# 13_Raspberry_Misc.net
KiCad netlist of a schematic drawn in Altium Designer
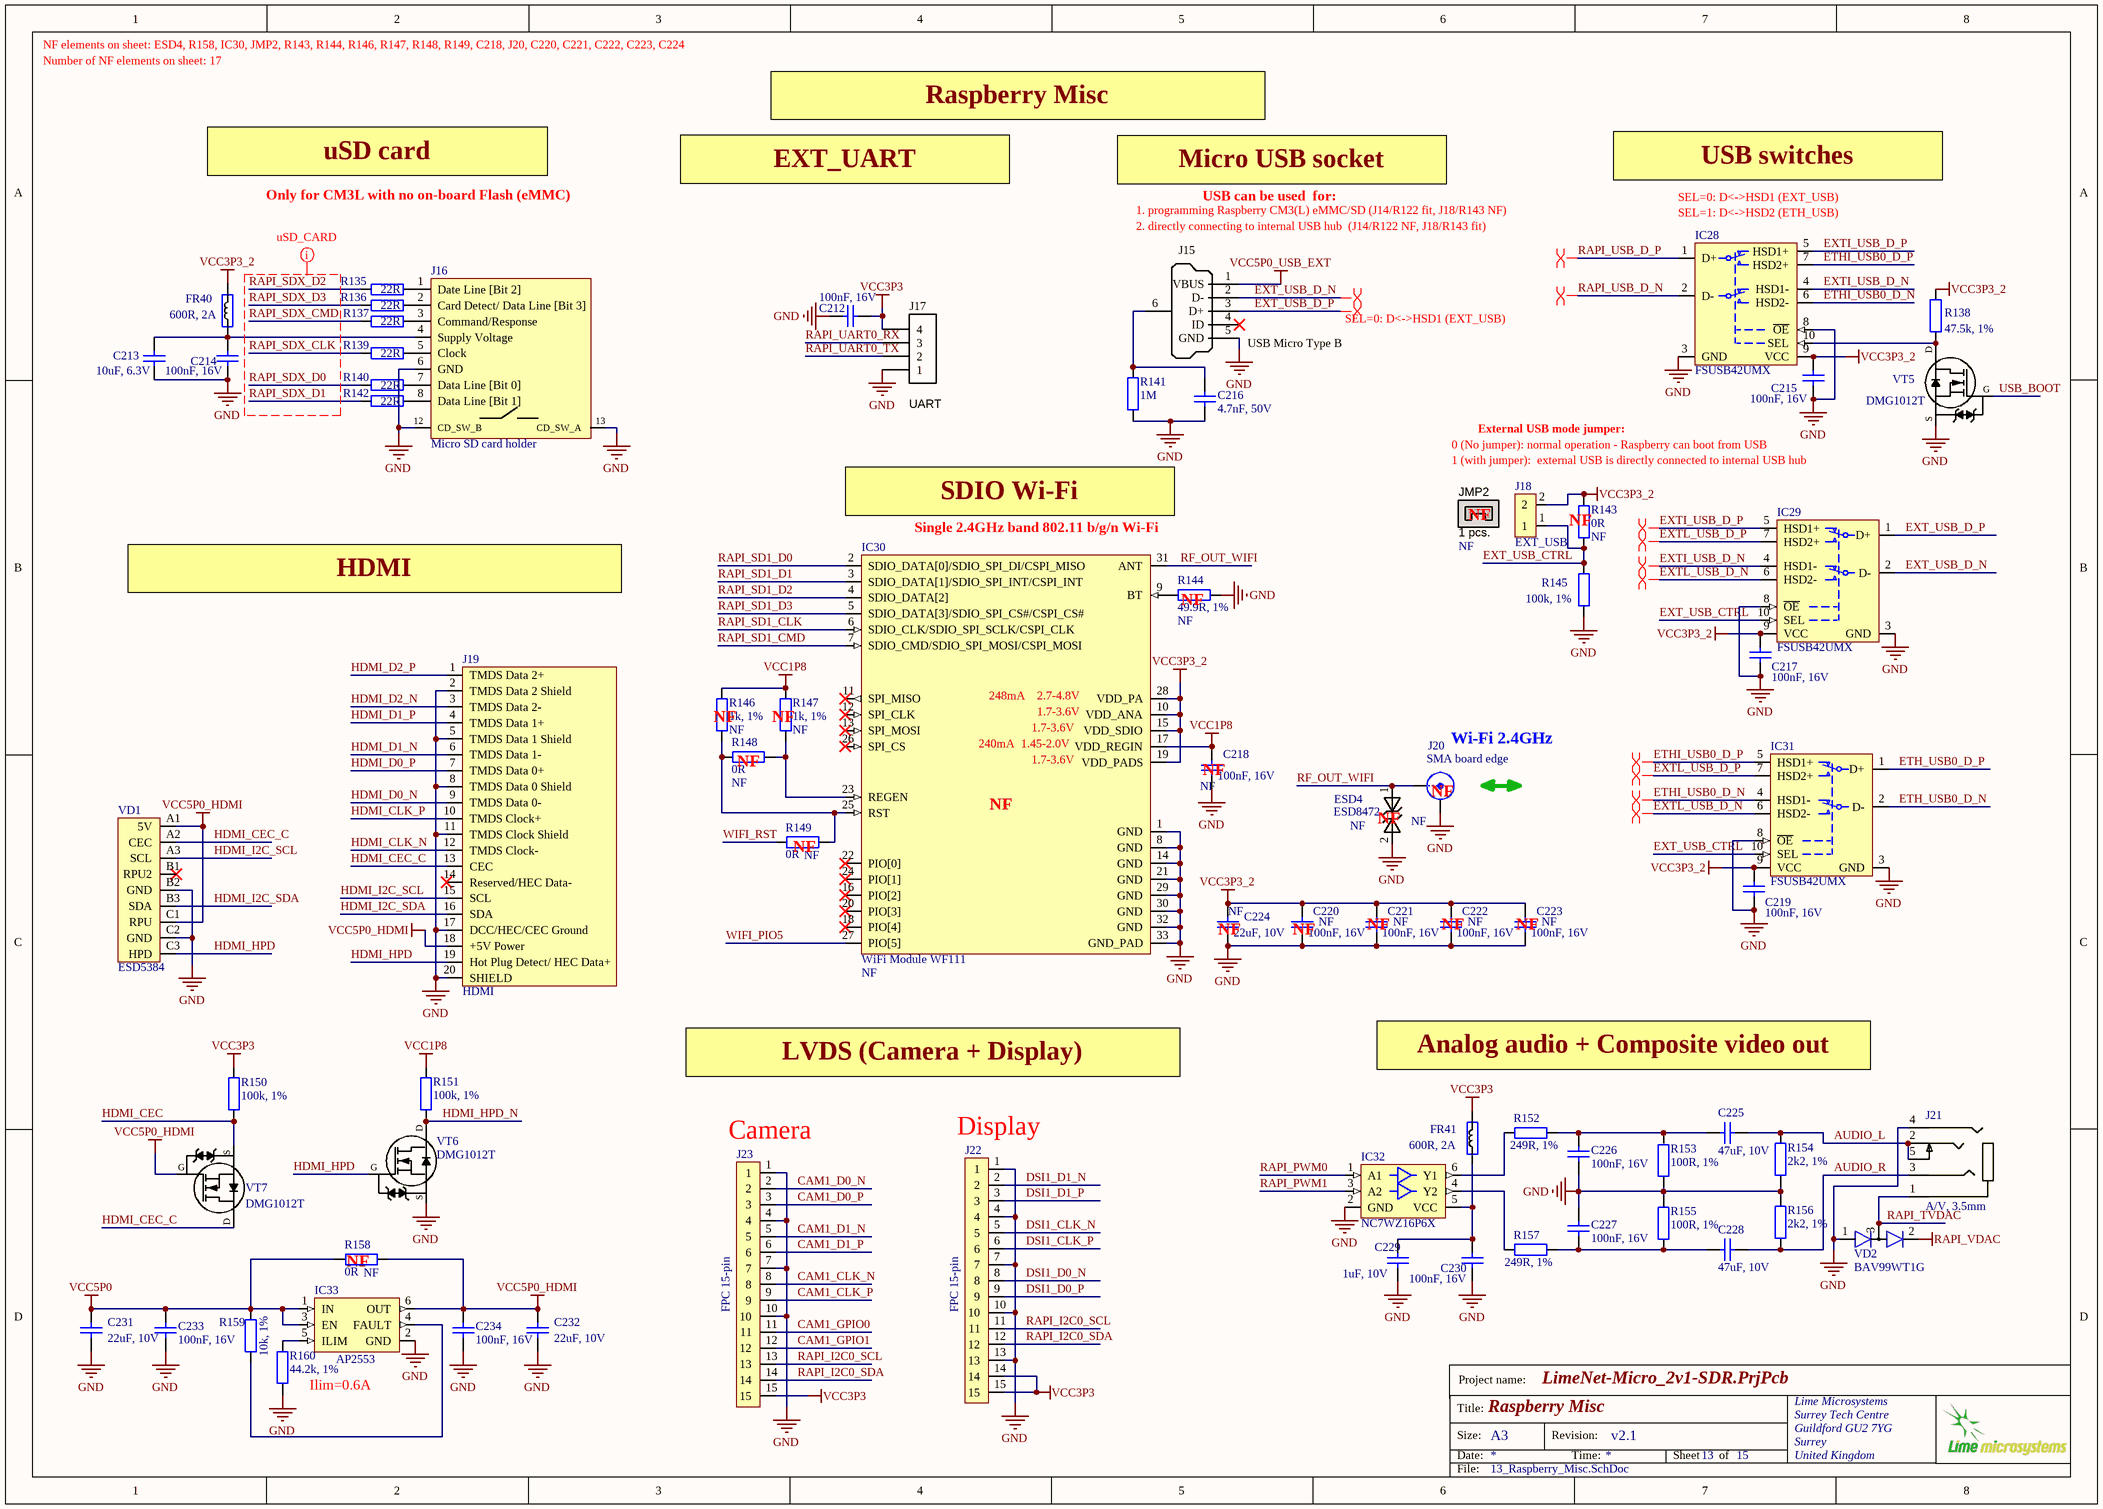
[diagram p0: 13_Raspberry_Misc.SchDoc]

(export (version "E")
  (design (tool "Eeschema 10.0.6"))
  (components
    (comp (ref "C212")
      (value "100nF, 16V")
      (footprint "CAP0402")
      (fields (field (name "TOLERANCE") "10 %") (field (name "MANUFACTURER") "Murata Electronics"))
      (libsource (lib "LimeFPGAboard_schLib") (part "Cap_0603"))
    )
    (comp (ref "C213")
      (value "10uF, 6.3V")
      (footprint "CAP0603")
      (fields (field (name "TOLERANCE") "±20%") (field (name "MANUFACTURER") "Yageo"))
      (libsource (lib "LimeFPGAboard_schLib") (part "Cap_0603"))
    )
    (comp (ref "C214")
      (value "100nF, 16V")
      (footprint "CAP0402")
      (fields (field (name "TOLERANCE") "10 %") (field (name "MANUFACTURER") "Murata Electronics"))
      (libsource (lib "LimeFPGAboard_schLib") (part "Cap_0603"))
    )
    (comp (ref "C215")
      (value "100nF, 16V")
      (footprint "CAP0402")
      (fields
        (field (name "MANUFACTURER") "Murata Electronics")
        (field (name "TOLERANCE") "10 %")
        (field (name "MANUFACTURER PART NUMBER") "GRM155R71C104KA88D")
      )
      (libsource (lib "LimeMicroAltiumLib_schLib") (part "Cap_0402"))
    )
    (comp (ref "C216")
      (value "4.7nF, 50V")
      (footprint "CAP0402")
      (fields
        (field (name "TOLERANCE") "±10%")
        (field (name "MANUFACTURER") "Murata Electronics North America")
      )
      (libsource (lib "LimeMicroAltiumLib_schLib") (part "Cap_0402"))
    )
    (comp (ref "C217")
      (value "100nF, 16V")
      (footprint "CAP0402")
      (fields
        (field (name "MANUFACTURER") "Murata Electronics")
        (field (name "TOLERANCE") "10 %")
        (field (name "MANUFACTURER PART NUMBER") "GRM155R71C104KA88D")
      )
      (libsource (lib "LimeMicroAltiumLib_schLib") (part "Cap_0402"))
    )
    (comp (ref "C218")
      (value "100nF, 16V")
      (footprint "CAP0402")
      (fields
        (field (name "ASSEMBLY INFO") "NF")
        (field (name "MANUFACTURER") "Murata Electronics")
        (field (name "TOLERANCE") "10 %")
        (field (name "MANUFACTURER PART NUMBER") "GRM155R71C104KA88D")
      )
      (libsource (lib "LimeMicroAltiumLib_schLib") (part "Cap_0402"))
    )
    (comp (ref "C219")
      (value "100nF, 16V")
      (footprint "CAP0402")
      (fields
        (field (name "MANUFACTURER") "Murata Electronics")
        (field (name "TOLERANCE") "10 %")
        (field (name "MANUFACTURER PART NUMBER") "GRM155R71C104KA88D")
      )
      (libsource (lib "LimeMicroAltiumLib_schLib") (part "Cap_0402"))
    )
    (comp (ref "C220")
      (value "100nF, 16V")
      (footprint "CAP0402")
      (fields
        (field (name "ASSEMBLY INFO") "NF")
        (field (name "MANUFACTURER") "Murata Electronics")
        (field (name "TOLERANCE") "10 %")
        (field (name "MANUFACTURER PART NUMBER") "GRM155R71C104KA88D")
      )
      (libsource (lib "LimeMicroAltiumLib_schLib") (part "Cap_0402"))
    )
    (comp (ref "C221")
      (value "100nF, 16V")
      (footprint "CAP0402")
      (fields
        (field (name "ASSEMBLY INFO") "NF")
        (field (name "MANUFACTURER") "Murata Electronics")
        (field (name "TOLERANCE") "10 %")
        (field (name "MANUFACTURER PART NUMBER") "GRM155R71C104KA88D")
      )
      (libsource (lib "LimeMicroAltiumLib_schLib") (part "Cap_0402"))
    )
    (comp (ref "C222")
      (value "100nF, 16V")
      (footprint "CAP0402")
      (fields
        (field (name "ASSEMBLY INFO") "NF")
        (field (name "MANUFACTURER") "Murata Electronics")
        (field (name "TOLERANCE") "10 %")
        (field (name "MANUFACTURER PART NUMBER") "GRM155R71C104KA88D")
      )
      (libsource (lib "LimeMicroAltiumLib_schLib") (part "Cap_0402"))
    )
    (comp (ref "C223")
      (value "100nF, 16V")
      (footprint "CAP0402")
      (fields
        (field (name "ASSEMBLY INFO") "NF")
        (field (name "MANUFACTURER") "Murata Electronics")
        (field (name "TOLERANCE") "10 %")
        (field (name "MANUFACTURER PART NUMBER") "GRM155R71C104KA88D")
      )
      (libsource (lib "LimeMicroAltiumLib_schLib") (part "Cap_0402"))
    )
    (comp (ref "C224")
      (value "22uF, 10V")
      (footprint "CAP0603")
      (fields
        (field (name "TOLERANCE") "20 %")
        (field (name "MANUFACTURER") "TDK Corporation")
        (field (name "ASSEMBLY INFO") "NF")
      )
      (libsource (lib "LimeFPGAboard_schLib") (part "Cap_0603"))
    )
    (comp (ref "C225")
      (value "47uF, 10V")
      (footprint "CAP1206")
      (fields (field (name "TOLERANCE") "±20%") (field (name "MANUFACTURER") "TDK Corporation"))
      (libsource (lib "LimeFPGAboard_schLib") (part "Cap_1206"))
    )
    (comp (ref "C226")
      (value "100nF, 16V")
      (footprint "CAP0402")
      (fields
        (field (name "MANUFACTURER") "Murata Electronics")
        (field (name "TOLERANCE") "10 %")
        (field (name "MANUFACTURER PART NUMBER") "GRM155R71C104KA88D")
      )
      (libsource (lib "LimeMicroAltiumLib_schLib") (part "Cap_0402"))
    )
    (comp (ref "C227")
      (value "100nF, 16V")
      (footprint "CAP0402")
      (fields
        (field (name "MANUFACTURER") "Murata Electronics")
        (field (name "TOLERANCE") "10 %")
        (field (name "MANUFACTURER PART NUMBER") "GRM155R71C104KA88D")
      )
      (libsource (lib "LimeMicroAltiumLib_schLib") (part "Cap_0402"))
    )
    (comp (ref "C228")
      (value "47uF, 10V")
      (footprint "CAP1206")
      (fields (field (name "TOLERANCE") "±20%") (field (name "MANUFACTURER") "TDK Corporation"))
      (libsource (lib "LimeFPGAboard_schLib") (part "Cap_1206"))
    )
    (comp (ref "C229")
      (value "1uF, 10V")
      (footprint "CAP0402")
      (description "CAP CER 1UF 10V X5R 0402")
      (fields (field (name "MANUFACTURER") "Yageo") (field (name "TOLERANCE") "±20%"))
      (libsource (lib "LimeMicroAltiumLib_schLib") (part "Cap_0402"))
    )
    (comp (ref "C230")
      (value "100nF, 16V")
      (footprint "CAP0402")
      (fields
        (field (name "MANUFACTURER") "Murata Electronics")
        (field (name "TOLERANCE") "10 %")
        (field (name "MANUFACTURER PART NUMBER") "GRM155R71C104KA88D")
      )
      (libsource (lib "LimeMicroAltiumLib_schLib") (part "Cap_0402"))
    )
    (comp (ref "C231")
      (value "22uF, 10V")
      (footprint "CAP0603")
      (fields (field (name "TOLERANCE") "20 %") (field (name "MANUFACTURER") "TDK Corporation"))
      (libsource (lib "LimeFPGAboard_schLib") (part "Cap_0603"))
    )
    (comp (ref "C232")
      (value "22uF, 10V")
      (footprint "CAP0603")
      (fields (field (name "TOLERANCE") "20 %") (field (name "MANUFACTURER") "TDK Corporation"))
      (libsource (lib "LimeFPGAboard_schLib") (part "Cap_0603"))
    )
    (comp (ref "C233")
      (value "100nF, 16V")
      (footprint "CAP0402")
      (fields
        (field (name "MANUFACTURER") "Murata Electronics")
        (field (name "TOLERANCE") "10 %")
        (field (name "MANUFACTURER PART NUMBER") "GRM155R71C104KA88D")
      )
      (libsource (lib "LimeMicroAltiumLib_schLib") (part "Cap_0402"))
    )
    (comp (ref "C234")
      (value "100nF, 16V")
      (footprint "CAP0402")
      (fields
        (field (name "MANUFACTURER") "Murata Electronics")
        (field (name "TOLERANCE") "10 %")
        (field (name "MANUFACTURER PART NUMBER") "GRM155R71C104KA88D")
      )
      (libsource (lib "LimeMicroAltiumLib_schLib") (part "Cap_0402"))
    )
    (comp (ref "ESD4")
      (value "ESD8472")
      (footprint "ESD8472_X3DFN2")
      (fields (field (name "MANUFACTURER") "ON Semiconductor") (field (name "ASSEMBLY INFO") "NF"))
      (libsource (lib "LimeMicroAltiumLib_schLib") (part "ESD8472"))
    )
    (comp (ref "FR40")
      (value "600R, 2A")
      (footprint "RES0805")
      (fields (field (name "MANUFACTURER") "TDK Corporation"))
      (libsource (lib "LimeMicroAltiumLib_schLib") (part "Ferrite"))
    )
    (comp (ref "FR41")
      (value "600R, 2A")
      (footprint "RES0805")
      (fields (field (name "MANUFACTURER") "TDK Corporation"))
      (libsource (lib "LimeMicroAltiumLib_schLib") (part "Ferrite"))
    )
    (comp (ref "IC28")
      (value "FSUSB42UMX")
      (footprint "FSUSB42UMX")
      (fields (field (name "MANUFACTURER") "ON Semiconductor") (field (name "BASE PART NUMBER") "FSUSB42"))
      (libsource (lib "") (part "FSUSB42UMX_1"))
    )
    (comp (ref "IC29")
      (value "FSUSB42UMX")
      (footprint "FSUSB42UMX")
      (fields (field (name "MANUFACTURER") "ON Semiconductor") (field (name "BASE PART NUMBER") "FSUSB42"))
      (libsource (lib "LimeMicroAltiumLib_schLib_r01") (part "FSUSB42UMX"))
    )
    (comp (ref "IC30")
      (value "WiFi Module WF111")
      (footprint "WF111-A-V1_WIFI")
      (fields (field (name "MANUFACTURER") "Bluegiga Technologies") (field (name "ASSEMBLY INFO") "NF"))
      (libsource (lib "LimeMicroAltiumLib_schLib_r01") (part "WF111-A-V1_WIFI"))
    )
    (comp (ref "IC31")
      (value "FSUSB42UMX")
      (footprint "FSUSB42UMX")
      (fields (field (name "MANUFACTURER") "ON Semiconductor") (field (name "BASE PART NUMBER") "FSUSB42"))
      (libsource (lib "LimeMicroAltiumLib_schLib_r01") (part "FSUSB42UMX"))
    )
    (comp (ref "IC32")
      (value "NC7WZ16P6X")
      (footprint "SC-70_NC7WZ16P6X")
      (fields (field (name "MANUFACTURER") "ON Semiconductor / Fairchild"))
      (libsource (lib "LimeMicroAltiumLib_schLib_r01") (part "NC7WZ16P6X_DUAL_BUFFER"))
    )
    (comp (ref "IC33")
      (value "AP2553")
      (footprint "SOT23-6")
      (fields (field (name "MANUFACTURER") "Diodes") (field (name "VOLTAGE") "5.5V"))
      (libsource (lib "LimeMicroAltiumLib_schLib_r01") (part "AP2553W6-7"))
    )
    (comp (ref "J15")
      (value "USB Micro Type B")
      (footprint "microUSB_v2")
      (description "Connector SMD USB Micro Type B")
      (fields (field (name "MANUFACTURER") "Amphenol FCI"))
      (libsource (lib "LimeMicroAltiumLib_schLib") (part "USB_Micro_TypeB"))
    )
    (comp (ref "J16")
      (value "Micro SD card holder")
      (footprint "MICRO_SD_CARD_114-00841-68_v2")
      (fields (field (name "MANUFACTURER") "Amphenol Commercial Products"))
      (libsource (lib "LimeMicroAltiumLib_schLib_r01") (part "MICRO_SD_114-00841-68"))
    )
    (comp (ref "J17")
      (value "UART")
      (footprint "HEADER4X1_TH")
      (description "Header, 4-pin")
      (fields (field (name "MANUFACTURER") "Wurth Electronics Inc."))
      (libsource (lib "LimeMicroAltiumLib_schLib") (part "Header4P"))
    )
    (comp (ref "J18")
      (value "EXT_USB")
      (footprint "HDR_1x2")
      (fields (field (name "MANUFACTURER") "3M"))
      (libsource (lib "LimeFPGAboard_schLib") (part "Jumper"))
    )
    (comp (ref "J19")
      (value "HDMI")
      (footprint "HDMI_AMPHENOL_10029449-111RLF")
      (fields (field (name "MANUFACTURER") "Amphenol FCI"))
      (libsource (lib "LimeMicroAltiumLib_schLib_r01") (part "HDMI_AMPHENOL_10029449-111RLF"))
    )
    (comp (ref "J20")
      (value "SMA board edge")
      (footprint "SMA_connector_board_edge_SM")
      (description "CONN SMA JACK STR 50OHM EDGE MNT")
      (fields (field (name "ASSEMBLY INFO") "NF") (field (name "MANUFACTURER") "RF Solutions"))
      (libsource (lib "LimeMicroAltiumLib_schLib") (part "RF_IF_connector"))
    )
    (comp (ref "J21")
      (value "A/V, 3.5mm")
      (footprint "Audio_jack_3.5mm")
      (fields (field (name "MANUFACTURER") "CUI Inc."))
      (libsource (lib "LimeMicroAltiumLib_schLib_r01") (part "AUDIO_JACK_3mm5_SJ-4351X"))
    )
    (comp (ref "J22")
      (value "FPC 15-pin")
      (footprint "FPC_CONNECTOR_15pin_1-1734248-5")
      (fields (field (name "MANUFACTURER") "TE Connectivity"))
      (libsource (lib "LimeMicroAltiumLib_schLib_r01") (part "FPC_CONNECTOR_15pin_1-1734248-5"))
    )
    (comp (ref "J23")
      (value "FPC 15-pin")
      (footprint "FPC_CONNECTOR_15pin_1-1734248-5")
      (fields (field (name "MANUFACTURER") "TE Connectivity"))
      (libsource (lib "LimeMicroAltiumLib_schLib_r01") (part "FPC_CONNECTOR_15pin_1-1734248-5"))
    )
    (comp (ref "JMP2")
      (value "1 pcs.")
      (description "Shorting Jumper, 2-position, 1.27mm pitch")
      (fields (field (name "ASSEMBLY INFO") "NF") (field (name "MANUFACTURER") "Sullins"))
      (libsource (lib "LimeMicroAltiumLib_schLib") (part "JUMP_2P_CONN_HEADER"))
    )
    (comp (ref "R135")
      (value "22R")
      (footprint "RES0402")
      (fields (field (name "TOLERANCE") "±1%") (field (name "MANUFACTURER") "Yageo"))
      (libsource (lib "LimeFPGAboard_schLib") (part "Res_0402"))
    )
    (comp (ref "R136")
      (value "22R")
      (footprint "RES0402")
      (fields (field (name "TOLERANCE") "±1%") (field (name "MANUFACTURER") "Yageo"))
      (libsource (lib "LimeFPGAboard_schLib") (part "Res_0402"))
    )
    (comp (ref "R137")
      (value "22R")
      (footprint "RES0402")
      (fields (field (name "TOLERANCE") "±1%") (field (name "MANUFACTURER") "Yageo"))
      (libsource (lib "LimeFPGAboard_schLib") (part "Res_0402"))
    )
    (comp (ref "R138")
      (value "47.5k, 1%")
      (footprint "RES0402")
      (fields (field (name "TOLERANCE") "±1%") (field (name "MANUFACTURER") "Yageo"))
      (libsource (lib "LimeMicroAltiumLib_schLib") (part "Res_0402"))
    )
    (comp (ref "R139")
      (value "22R")
      (footprint "RES0402")
      (fields (field (name "TOLERANCE") "±1%") (field (name "MANUFACTURER") "Yageo"))
      (libsource (lib "LimeFPGAboard_schLib") (part "Res_0402"))
    )
    (comp (ref "R140")
      (value "22R")
      (footprint "RES0402")
      (fields (field (name "TOLERANCE") "±1%") (field (name "MANUFACTURER") "Yageo"))
      (libsource (lib "LimeFPGAboard_schLib") (part "Res_0402"))
    )
    (comp (ref "R141")
      (value "1M")
      (footprint "RES0402")
      (fields (field (name "MANUFACTURER") "TE CONNECTIVITY"))
      (libsource (lib "LimeMicroAltiumLib_schLib") (part "Res_0402"))
    )
    (comp (ref "R142")
      (value "22R")
      (footprint "RES0402")
      (fields (field (name "TOLERANCE") "±1%") (field (name "MANUFACTURER") "Yageo"))
      (libsource (lib "LimeFPGAboard_schLib") (part "Res_0402"))
    )
    (comp (ref "R143")
      (value "0R")
      (footprint "RES0402")
      (fields
        (field (name "ASSEMBLY INFO") "NF")
        (field (name "MANUFACTURER") "Yageo")
        (field (name "TOLERANCE") "Jumper")
      )
      (libsource (lib "LimeMicroAltiumLib_schLib") (part "Res_0402"))
    )
    (comp (ref "R144")
      (value "49.9R, 1%")
      (footprint "RES0402")
      (fields
        (field (name "ASSEMBLY INFO") "NF")
        (field (name "TOLERANCE") "±1%")
        (field (name "MANUFACTURER") "Samsung Electro-Mechanics America, Inc.")
      )
      (libsource (lib "LimeMicroAltiumLib_schLib") (part "Res_0402"))
    )
    (comp (ref "R145")
      (value "100k, 1%")
      (footprint "RES0402")
      (fields
        (field (name "MANUFACTURER") "Vishay Dale")
        (field (name "TOLERANCE") "±1%")
        (field (name "MANUFACTURER PART NUMBER") "CRCW0402100KFKEDC")
      )
      (libsource (lib "LimeMicroAltiumLib_schLib") (part "Res_0402"))
    )
    (comp (ref "R146")
      (value "1k, 1%")
      (footprint "RES0402")
      (fields
        (field (name "ASSEMBLY INFO") "NF")
        (field (name "MANUFACTURER") "Stackpole Electronics Inc")
        (field (name "TOLERANCE") "±1%")
      )
      (libsource (lib "LimeMicroAltiumLib_schLib") (part "Res_0402"))
    )
    (comp (ref "R147")
      (value "1k, 1%")
      (footprint "RES0402")
      (fields
        (field (name "ASSEMBLY INFO") "NF")
        (field (name "MANUFACTURER") "Stackpole Electronics Inc")
        (field (name "TOLERANCE") "±1%")
      )
      (libsource (lib "LimeMicroAltiumLib_schLib") (part "Res_0402"))
    )
    (comp (ref "R148")
      (value "0R")
      (footprint "RES0402")
      (fields
        (field (name "ASSEMBLY INFO") "NF")
        (field (name "MANUFACTURER") "Yageo")
        (field (name "TOLERANCE") "Jumper")
      )
      (libsource (lib "LimeMicroAltiumLib_schLib") (part "Res_0402"))
    )
    (comp (ref "R149")
      (value "0R")
      (footprint "RES0402")
      (fields
        (field (name "ASSEMBLY INFO") "NF")
        (field (name "MANUFACTURER") "Yageo")
        (field (name "TOLERANCE") "Jumper")
      )
      (libsource (lib "LimeMicroAltiumLib_schLib") (part "Res_0402"))
    )
    (comp (ref "R150")
      (value "100k, 1%")
      (footprint "RES0402")
      (fields
        (field (name "MANUFACTURER") "Vishay Dale")
        (field (name "TOLERANCE") "±1%")
        (field (name "MANUFACTURER PART NUMBER") "CRCW0402100KFKEDC")
      )
      (libsource (lib "LimeMicroAltiumLib_schLib") (part "Res_0402"))
    )
    (comp (ref "R151")
      (value "100k, 1%")
      (footprint "RES0402")
      (fields
        (field (name "MANUFACTURER") "Vishay Dale")
        (field (name "TOLERANCE") "±1%")
        (field (name "MANUFACTURER PART NUMBER") "CRCW0402100KFKEDC")
      )
      (libsource (lib "LimeMicroAltiumLib_schLib") (part "Res_0402"))
    )
    (comp (ref "R152")
      (value "249R, 1%")
      (footprint "RES0402")
      (fields (field (name "MANUFACTURER") "Stackpole Electronics Inc") (field (name "TOLERANCE") "±1%"))
      (libsource (lib "LimeMicroAltiumLib_schLib") (part "Res_0402"))
    )
    (comp (ref "R153")
      (value "100R, 1%")
      (footprint "RES0402")
      (fields (field (name "TOLERANCE") "±1%") (field (name "MANUFACTURER") "Stackpole Electronics Inc."))
      (libsource (lib "LimeMicroAltiumLib_schLib") (part "Res_0402"))
    )
    (comp (ref "R154")
      (value "2k2, 1%")
      (footprint "RES0402")
      (fields (field (name "MANUFACTURER") "Stackpole Electronics Inc") (field (name "TOLERANCE") "±1%"))
      (libsource (lib "LimeMicroAltiumLib_schLib") (part "Res_0402"))
    )
    (comp (ref "R155")
      (value "100R, 1%")
      (footprint "RES0402")
      (fields (field (name "TOLERANCE") "±1%") (field (name "MANUFACTURER") "Stackpole Electronics Inc."))
      (libsource (lib "LimeMicroAltiumLib_schLib") (part "Res_0402"))
    )
    (comp (ref "R156")
      (value "2k2, 1%")
      (footprint "RES0402")
      (fields (field (name "MANUFACTURER") "Stackpole Electronics Inc") (field (name "TOLERANCE") "±1%"))
      (libsource (lib "LimeMicroAltiumLib_schLib") (part "Res_0402"))
    )
    (comp (ref "R157")
      (value "249R, 1%")
      (footprint "RES0402")
      (fields (field (name "MANUFACTURER") "Stackpole Electronics Inc") (field (name "TOLERANCE") "±1%"))
      (libsource (lib "LimeMicroAltiumLib_schLib") (part "Res_0402"))
    )
    (comp (ref "R158")
      (value "0R")
      (footprint "RES0402_v2")
      (fields
        (field (name "ASSEMBLY INFO") "NF")
        (field (name "MANUFACTURER") "Yageo")
        (field (name "TOLERANCE") "Jumper")
      )
      (libsource (lib "LimeMicroAltiumLib_schLib") (part "Res_0402"))
    )
    (comp (ref "R159")
      (value "10k, 1%")
      (footprint "RES0402")
      (fields (field (name "MANUFACTURER") "Yageo") (field (name "TOLERANCE") "±1%"))
      (libsource (lib "LimeMicroAltiumLib_schLib") (part "Res_0402"))
    )
    (comp (ref "R160")
      (value "44.2k, 1%")
      (footprint "RES0402")
      (fields
        (field (name "TOLERANCE") "±1%")
        (field (name "MANUFACTURER") "Panasonic Electronic Components")
      )
      (libsource (lib "LimeMicroAltiumLib_schLib") (part "Res_0402"))
    )
    (comp (ref "VD1")
      (value "ESD5384")
      (footprint "TVS_ESD5384NCTBG")
      (fields (field (name "MANUFACTURER") "ON Semiconductor"))
      (libsource (lib "LimeMicroAltiumLib_schLib_r01") (part "TVS_ESD5384NCTBG"))
    )
    (comp (ref "VD2")
      (value "BAV99WT1G")
      (footprint "SC-70_BAV99WT1G")
      (fields (field (name "MANUFACTURER") "ON Semiconductor"))
      (libsource (lib "LimeMicroAltiumLib_schLib_r01") (part "BAV99WT1G_DUAL_DIODE"))
    )
    (comp (ref "VT5")
      (value "DMG1012T")
      (footprint "SOT523")
      (fields (field (name "MANUFACTURER") "Diodes Incorporated"))
      (libsource (lib "LimeMicroAltiumLib_schLib_r01") (part "DMG1012T"))
    )
    (comp (ref "VT6")
      (value "DMG1012T")
      (footprint "SOT523")
      (fields (field (name "MANUFACTURER") "Diodes Incorporated"))
      (libsource (lib "LimeMicroAltiumLib_schLib_r01") (part "DMG1012T"))
    )
    (comp (ref "VT7")
      (value "DMG1012T")
      (footprint "SOT523")
      (fields (field (name "MANUFACTURER") "Diodes Incorporated"))
      (libsource (lib "LimeMicroAltiumLib_schLib_r01") (part "DMG1012T"))
    )
  )
  (nets
    (net (code "1") (name "/AUDIO_L") (class "Default")
      (node (ref "C225") (pin "1") (pinfunction "1_1") (pintype "passive"))
      (node (ref "J21") (pin "2") (pinfunction "2_2") (pintype "passive"))
      (node (ref "J21") (pin "5") (pinfunction "5_5") (pintype "passive"))
      (node (ref "R154") (pin "1") (pinfunction "1_1") (pintype "passive"))
    )
    (net (code "2") (name "/AUDIO_R") (class "Default")
      (node (ref "C228") (pin "1") (pinfunction "1_1") (pintype "passive"))
      (node (ref "J21") (pin "3") (pinfunction "3_3") (pintype "passive"))
      (node (ref "R156") (pin "2") (pinfunction "2_2") (pintype "passive"))
    )
    (net (code "3") (name "/CAM1_CLK_N") (class "Default")
      (node (ref "J23") (pin "8") (pinfunction "8_8") (pintype "passive"))
    )
    (net (code "4") (name "/CAM1_CLK_P") (class "Default")
      (node (ref "J23") (pin "9") (pinfunction "9_9") (pintype "passive"))
    )
    (net (code "5") (name "/CAM1_D0_N") (class "Default")
      (node (ref "J23") (pin "2") (pinfunction "2_2") (pintype "passive"))
    )
    (net (code "6") (name "/CAM1_D0_P") (class "Default")
      (node (ref "J23") (pin "3") (pinfunction "3_3") (pintype "passive"))
    )
    (net (code "7") (name "/CAM1_D1_N") (class "Default")
      (node (ref "J23") (pin "5") (pinfunction "5_5") (pintype "passive"))
    )
    (net (code "8") (name "/CAM1_D1_P") (class "Default")
      (node (ref "J23") (pin "6") (pinfunction "6_6") (pintype "passive"))
    )
    (net (code "9") (name "/CAM1_GPIO0") (class "Default")
      (node (ref "J23") (pin "11") (pinfunction "11_11") (pintype "passive"))
    )
    (net (code "10") (name "/CAM1_GPIO1") (class "Default")
      (node (ref "J23") (pin "12") (pinfunction "12_12") (pintype "passive"))
    )
    (net (code "11") (name "/DSI1_CLK_N") (class "Default")
      (node (ref "J22") (pin "5") (pinfunction "5_5") (pintype "passive"))
    )
    (net (code "12") (name "/DSI1_CLK_P") (class "Default")
      (node (ref "J22") (pin "6") (pinfunction "6_6") (pintype "passive"))
    )
    (net (code "13") (name "/DSI1_D0_N") (class "Default")
      (node (ref "J22") (pin "8") (pinfunction "8_8") (pintype "passive"))
    )
    (net (code "14") (name "/DSI1_D0_P") (class "Default")
      (node (ref "J22") (pin "9") (pinfunction "9_9") (pintype "passive"))
    )
    (net (code "15") (name "/DSI1_D1_N") (class "Default")
      (node (ref "J22") (pin "2") (pinfunction "2_2") (pintype "passive"))
    )
    (net (code "16") (name "/DSI1_D1_P") (class "Default")
      (node (ref "J22") (pin "3") (pinfunction "3_3") (pintype "passive"))
    )
    (net (code "17") (name "/ETHI_USB0_D_N") (class "Default")
      (node (ref "IC28") (pin "6") (pinfunction "HSD2-_6") (pintype "passive"))
      (node (ref "IC31") (pin "4") (pinfunction "HSD1-_4") (pintype "passive"))
    )
    (net (code "18") (name "/ETHI_USB0_D_P") (class "Default")
      (node (ref "IC28") (pin "7") (pinfunction "HSD2+_7") (pintype "passive"))
      (node (ref "IC31") (pin "5") (pinfunction "HSD1+_5") (pintype "passive"))
    )
    (net (code "19") (name "/ETH_USB0_D_N") (class "Default")
      (node (ref "IC31") (pin "2") (pinfunction "D-_2") (pintype "passive"))
    )
    (net (code "20") (name "/ETH_USB0_D_P") (class "Default")
      (node (ref "IC31") (pin "1") (pinfunction "D+_1") (pintype "passive"))
    )
    (net (code "21") (name "/EXTI_USB_D_N") (class "Default")
      (node (ref "IC28") (pin "4") (pinfunction "HSD1-_4") (pintype "passive"))
      (node (ref "IC29") (pin "4") (pinfunction "HSD1-_4") (pintype "passive"))
    )
    (net (code "22") (name "/EXTI_USB_D_P") (class "Default")
      (node (ref "IC28") (pin "5") (pinfunction "HSD1+_5") (pintype "passive"))
      (node (ref "IC29") (pin "5") (pinfunction "HSD1+_5") (pintype "passive"))
    )
    (net (code "23") (name "/EXTL_USB_D_N") (class "Default")
      (node (ref "IC29") (pin "6") (pinfunction "HSD2-_6") (pintype "passive"))
      (node (ref "IC31") (pin "6") (pinfunction "HSD2-_6") (pintype "passive"))
    )
    (net (code "24") (name "/EXTL_USB_D_P") (class "Default")
      (node (ref "IC29") (pin "7") (pinfunction "HSD2+_7") (pintype "passive"))
      (node (ref "IC31") (pin "7") (pinfunction "HSD2+_7") (pintype "passive"))
    )
    (net (code "25") (name "/EXT_USB_CTRL") (class "Default")
      (node (ref "IC29") (pin "10") (pinfunction "SEL_10") (pintype "input"))
      (node (ref "IC31") (pin "10") (pinfunction "SEL_10") (pintype "input"))
      (node (ref "J18") (pin "1") (pinfunction "1_1") (pintype "passive"))
      (node (ref "R143") (pin "1") (pinfunction "1_1") (pintype "passive"))
      (node (ref "R145") (pin "1") (pinfunction "1_1") (pintype "passive"))
    )
    (net (code "26") (name "/EXT_USB_D_N") (class "Default")
      (node (ref "IC29") (pin "2") (pinfunction "D-_2") (pintype "passive"))
      (node (ref "J15") (pin "2") (pinfunction "D-_2") (pintype "passive"))
    )
    (net (code "27") (name "/EXT_USB_D_P") (class "Default")
      (node (ref "IC29") (pin "1") (pinfunction "D+_1") (pintype "passive"))
      (node (ref "J15") (pin "3") (pinfunction "D+_3") (pintype "passive"))
    )
    (net (code "28") (name "/HDMI_CEC") (class "Default")
      (node (ref "R150") (pin "2") (pinfunction "2_2") (pintype "passive"))
      (node (ref "VT7") (pin "S") (pinfunction "S_S") (pintype "passive"))
    )
    (net (code "29") (name "/HDMI_CEC_C") (class "Default")
      (node (ref "J19") (pin "13") (pinfunction "CEC_13") (pintype "passive"))
      (node (ref "VD1") (pin "A2") (pinfunction "CEC_A2") (pintype "passive"))
      (node (ref "VT7") (pin "D") (pinfunction "D_D") (pintype "passive"))
    )
    (net (code "30") (name "/HDMI_CLK_N") (class "Default")
      (node (ref "J19") (pin "12") (pinfunction "TMDS_Clock-_12") (pintype "passive"))
    )
    (net (code "31") (name "/HDMI_CLK_P") (class "Default")
      (node (ref "J19") (pin "10") (pinfunction "TMDS_Clock+_10") (pintype "passive"))
    )
    (net (code "32") (name "/HDMI_D0_N") (class "Default")
      (node (ref "J19") (pin "9") (pinfunction "TMDS_Data_0-_9") (pintype "passive"))
    )
    (net (code "33") (name "/HDMI_D0_P") (class "Default")
      (node (ref "J19") (pin "7") (pinfunction "TMDS_Data_0+_7") (pintype "passive"))
    )
    (net (code "34") (name "/HDMI_D1_N") (class "Default")
      (node (ref "J19") (pin "6") (pinfunction "TMDS_Data_1-_6") (pintype "passive"))
    )
    (net (code "35") (name "/HDMI_D1_P") (class "Default")
      (node (ref "J19") (pin "4") (pinfunction "TMDS_Data_1+_4") (pintype "passive"))
    )
    (net (code "36") (name "/HDMI_D2_N") (class "Default")
      (node (ref "J19") (pin "3") (pinfunction "TMDS_Data_2-_3") (pintype "passive"))
    )
    (net (code "37") (name "/HDMI_D2_P") (class "Default")
      (node (ref "J19") (pin "1") (pinfunction "TMDS_Data_2+_1") (pintype "passive"))
    )
    (net (code "38") (name "/HDMI_HPD") (class "Default")
      (node (ref "J19") (pin "19") (pinfunction "Hot_Plug_Detect/_HEC_Data+_19") (pintype "passive"))
      (node (ref "VD1") (pin "C3") (pinfunction "HPD_C3") (pintype "passive"))
      (node (ref "VT6") (pin "G") (pinfunction "G_G") (pintype "passive"))
    )
    (net (code "39") (name "/HDMI_HPD_N") (class "Default")
      (node (ref "R151") (pin "2") (pinfunction "2_2") (pintype "passive"))
      (node (ref "VT6") (pin "D") (pinfunction "D_D") (pintype "passive"))
    )
    (net (code "40") (name "/HDMI_I2C_SCL") (class "Default")
      (node (ref "J19") (pin "15") (pinfunction "SCL_15") (pintype "passive"))
      (node (ref "VD1") (pin "A3") (pinfunction "SCL_A3") (pintype "passive"))
    )
    (net (code "41") (name "/HDMI_I2C_SDA") (class "Default")
      (node (ref "J19") (pin "16") (pinfunction "SDA_16") (pintype "passive"))
      (node (ref "VD1") (pin "B3") (pinfunction "SDA_B3") (pintype "passive"))
    )
    (net (code "42") (name "/RAPI_I2C0_SCL") (class "Default")
      (node (ref "J22") (pin "11") (pinfunction "11_11") (pintype "passive"))
      (node (ref "J23") (pin "13") (pinfunction "13_13") (pintype "passive"))
    )
    (net (code "43") (name "/RAPI_I2C0_SDA") (class "Default")
      (node (ref "J22") (pin "12") (pinfunction "12_12") (pintype "passive"))
      (node (ref "J23") (pin "14") (pinfunction "14_14") (pintype "passive"))
    )
    (net (code "44") (name "/RAPI_PWM0") (class "Default")
      (node (ref "IC32") (pin "1") (pinfunction "A1_1") (pintype "input"))
    )
    (net (code "45") (name "/RAPI_PWM1") (class "Default")
      (node (ref "IC32") (pin "3") (pinfunction "A2_3") (pintype "input"))
    )
    (net (code "46") (name "/RAPI_SD1_CLK") (class "Default")
      (node (ref "IC30") (pin "6") (pinfunction "SDIO_CLK/SDIO_SPI_SCLK/CSPI_CLK_6") (pintype "input"))
    )
    (net (code "47") (name "/RAPI_SD1_CMD") (class "Default")
      (node (ref "IC30") (pin "7") (pinfunction "SDIO_CMD/SDIO_SPI_MOSI/CSPI_MOSI_7") (pintype "input"))
    )
    (net (code "48") (name "/RAPI_SD1_D0") (class "Default")
      (node (ref "IC30") (pin "2") (pinfunction "SDIO_DATA[0]/SDIO_SPI_DI/CSPI_MISO_2") (pintype "bidirectional"))
    )
    (net (code "49") (name "/RAPI_SD1_D1") (class "Default")
      (node (ref "IC30") (pin "3") (pinfunction "SDIO_DATA[1]/SDIO_SPI_INT/CSPI_INT_3") (pintype "bidirectional"))
    )
    (net (code "50") (name "/RAPI_SD1_D2") (class "Default")
      (node (ref "IC30") (pin "4") (pinfunction "SDIO_DATA[2]_4") (pintype "bidirectional"))
    )
    (net (code "51") (name "/RAPI_SD1_D3") (class "Default")
      (node (ref "IC30") (pin "5") (pinfunction "SDIO_DATA[3]/SDIO_SPI_CS#/CSPI_CS#_5") (pintype "bidirectional"))
    )
    (net (code "52") (name "/RAPI_SDX_CLK") (class "Default")
      (node (ref "R139") (pin "1") (pinfunction "1_1") (pintype "passive"))
    )
    (net (code "53") (name "/RAPI_SDX_CMD") (class "Default")
      (node (ref "R137") (pin "1") (pinfunction "1_1") (pintype "passive"))
    )
    (net (code "54") (name "/RAPI_SDX_D0") (class "Default")
      (node (ref "R140") (pin "1") (pinfunction "1_1") (pintype "passive"))
    )
    (net (code "55") (name "/RAPI_SDX_D1") (class "Default")
      (node (ref "R142") (pin "1") (pinfunction "1_1") (pintype "passive"))
    )
    (net (code "56") (name "/RAPI_SDX_D2") (class "Default")
      (node (ref "R135") (pin "1") (pinfunction "1_1") (pintype "passive"))
    )
    (net (code "57") (name "/RAPI_SDX_D3") (class "Default")
      (node (ref "R136") (pin "1") (pinfunction "1_1") (pintype "passive"))
    )
    (net (code "58") (name "/RAPI_TVDAC") (class "Default")
      (node (ref "J21") (pin "1") (pinfunction "1_1") (pintype "passive"))
      (node (ref "VD2") (pin "3") (pinfunction "3_3") (pintype "passive"))
    )
    (net (code "59") (name "/RAPI_UART0_RX") (class "Default")
      (node (ref "J17") (pin "3") (pinfunction "3_3") (pintype "passive"))
    )
    (net (code "60") (name "/RAPI_UART0_TX") (class "Default")
      (node (ref "J17") (pin "2") (pinfunction "2_2") (pintype "passive"))
    )
    (net (code "61") (name "/RAPI_USB_D_N") (class "Default")
      (node (ref "IC28") (pin "2") (pinfunction "D-_2") (pintype "passive"))
    )
    (net (code "62") (name "/RAPI_USB_D_P") (class "Default")
      (node (ref "IC28") (pin "1") (pinfunction "D+_1") (pintype "passive"))
    )
    (net (code "63") (name "/RF_OUT_WIFI") (class "Default")
      (node (ref "ESD4") (pin "1") (pinfunction "1_1") (pintype "passive"))
      (node (ref "IC30") (pin "31") (pinfunction "ANT_31") (pintype "passive"))
      (node (ref "J20") (pin "1") (pinfunction "X_1") (pintype "passive"))
    )
    (net (code "64") (name "/USB_BOOT") (class "Default")
      (node (ref "VT5") (pin "G") (pinfunction "G_G") (pintype "passive"))
    )
    (net (code "65") (name "/WIFI_PIO5") (class "Default")
      (node (ref "IC30") (pin "27") (pinfunction "PIO[5]_27") (pintype "bidirectional"))
    )
    (net (code "66") (name "/WIFI_RST") (class "Default")
      (node (ref "R149") (pin "1") (pinfunction "1_1") (pintype "passive"))
    )
    (net (code "67") (name "GND") (class "Default")
      (node (ref "C212") (pin "2") (pinfunction "2_2") (pintype "passive"))
      (node (ref "C213") (pin "1") (pinfunction "1_1") (pintype "passive"))
      (node (ref "C214") (pin "2") (pinfunction "2_2") (pintype "passive"))
      (node (ref "C215") (pin "2") (pinfunction "2_2") (pintype "passive"))
      (node (ref "C216") (pin "2") (pinfunction "2_2") (pintype "passive"))
      (node (ref "C217") (pin "2") (pinfunction "2_2") (pintype "passive"))
      (node (ref "C218") (pin "1") (pinfunction "1_1") (pintype "passive"))
      (node (ref "C219") (pin "2") (pinfunction "2_2") (pintype "passive"))
      (node (ref "C220") (pin "1") (pinfunction "1_1") (pintype "passive"))
      (node (ref "C221") (pin "1") (pinfunction "1_1") (pintype "passive"))
      (node (ref "C222") (pin "1") (pinfunction "1_1") (pintype "passive"))
      (node (ref "C223") (pin "1") (pinfunction "1_1") (pintype "passive"))
      (node (ref "C224") (pin "1") (pinfunction "1_1") (pintype "passive"))
      (node (ref "C226") (pin "2") (pinfunction "2_2") (pintype "passive"))
      (node (ref "C227") (pin "1") (pinfunction "1_1") (pintype "passive"))
      (node (ref "C229") (pin "1") (pinfunction "1_1") (pintype "passive"))
      (node (ref "C230") (pin "2") (pinfunction "2_2") (pintype "passive"))
      (node (ref "C231") (pin "1") (pinfunction "1_1") (pintype "passive"))
      (node (ref "C232") (pin "1") (pinfunction "1_1") (pintype "passive"))
      (node (ref "C233") (pin "2") (pinfunction "2_2") (pintype "passive"))
      (node (ref "C234") (pin "2") (pinfunction "2_2") (pintype "passive"))
      (node (ref "ESD4") (pin "2") (pinfunction "2_2") (pintype "passive"))
      (node (ref "IC28") (pin "3") (pinfunction "GND_3") (pintype "passive"))
      (node (ref "IC28") (pin "8") (pinfunction "~{OE}_8") (pintype "input"))
      (node (ref "IC29") (pin "3") (pinfunction "GND_3") (pintype "passive"))
      (node (ref "IC29") (pin "8") (pinfunction "~{OE}_8") (pintype "input"))
      (node (ref "IC30") (pin "1") (pinfunction "GND_1") (pintype "passive"))
      (node (ref "IC30") (pin "14") (pinfunction "GND_14") (pintype "passive"))
      (node (ref "IC30") (pin "21") (pinfunction "GND_21") (pintype "passive"))
      (node (ref "IC30") (pin "29") (pinfunction "GND_29") (pintype "passive"))
      (node (ref "IC30") (pin "30") (pinfunction "GND_30") (pintype "passive"))
      (node (ref "IC30") (pin "32") (pinfunction "GND_32") (pintype "passive"))
      (node (ref "IC30") (pin "33") (pinfunction "GND_PAD_33") (pintype "passive"))
      (node (ref "IC30") (pin "8") (pinfunction "GND_8") (pintype "passive"))
      (node (ref "IC31") (pin "3") (pinfunction "GND_3") (pintype "passive"))
      (node (ref "IC31") (pin "8") (pinfunction "~{OE}_8") (pintype "input"))
      (node (ref "IC32") (pin "2") (pinfunction "GND_2") (pintype "passive"))
      (node (ref "IC33") (pin "2") (pinfunction "GND_2") (pintype "passive"))
      (node (ref "J15") (pin "5") (pinfunction "GND_5") (pintype "passive"))
      (node (ref "J16") (pin "12") (pinfunction "CD_SW_B_12") (pintype "passive"))
      (node (ref "J16") (pin "13") (pinfunction "CD_SW_A_13") (pintype "passive"))
      (node (ref "J16") (pin "6") (pinfunction "GND_6") (pintype "passive"))
      (node (ref "J17") (pin "1") (pinfunction "1_1") (pintype "passive"))
      (node (ref "J19") (pin "11") (pinfunction "TMDS_Clock_Shield_11") (pintype "passive"))
      (node (ref "J19") (pin "17") (pinfunction "DCC/HEC/CEC_Ground_17") (pintype "passive"))
      (node (ref "J19") (pin "2") (pinfunction "TMDS_Data_2_Shield_2") (pintype "passive"))
      (node (ref "J19") (pin "20") (pinfunction "SHIELD_20") (pintype "passive"))
      (node (ref "J19") (pin "5") (pinfunction "TMDS_Data_1_Shield_5") (pintype "passive"))
      (node (ref "J19") (pin "8") (pinfunction "TMDS_Data_0_Shield_8") (pintype "passive"))
      (node (ref "J20") (pin "2") (pinfunction "Y_2") (pintype "passive"))
      (node (ref "J21") (pin "4") (pinfunction "4_4") (pintype "passive"))
      (node (ref "J22") (pin "1") (pinfunction "1_1") (pintype "passive"))
      (node (ref "J22") (pin "10") (pinfunction "10_10") (pintype "passive"))
      (node (ref "J22") (pin "13") (pinfunction "13_13") (pintype "passive"))
      (node (ref "J22") (pin "4") (pinfunction "4_4") (pintype "passive"))
      (node (ref "J22") (pin "7") (pinfunction "7_7") (pintype "passive"))
      (node (ref "J23") (pin "1") (pinfunction "1_1") (pintype "passive"))
      (node (ref "J23") (pin "10") (pinfunction "10_10") (pintype "passive"))
      (node (ref "J23") (pin "4") (pinfunction "4_4") (pintype "passive"))
      (node (ref "J23") (pin "7") (pinfunction "7_7") (pintype "passive"))
      (node (ref "R141") (pin "2") (pinfunction "2_2") (pintype "passive"))
      (node (ref "R144") (pin "1") (pinfunction "1_1") (pintype "passive"))
      (node (ref "R145") (pin "2") (pinfunction "2_2") (pintype "passive"))
      (node (ref "R153") (pin "1") (pinfunction "1_1") (pintype "passive"))
      (node (ref "R154") (pin "2") (pinfunction "2_2") (pintype "passive"))
      (node (ref "R155") (pin "2") (pinfunction "2_2") (pintype "passive"))
      (node (ref "R156") (pin "1") (pinfunction "1_1") (pintype "passive"))
      (node (ref "R160") (pin "2") (pinfunction "2_2") (pintype "passive"))
      (node (ref "VD1") (pin "B2") (pinfunction "GND_B2") (pintype "passive"))
      (node (ref "VD1") (pin "C2") (pinfunction "GND_C2") (pintype "passive"))
      (node (ref "VD2") (pin "1") (pinfunction "1_1") (pintype "passive"))
      (node (ref "VT5") (pin "S") (pinfunction "S_S") (pintype "passive"))
      (node (ref "VT6") (pin "S") (pinfunction "S_S") (pintype "passive"))
    )
    (net (code "68") (name "Net-(C225-Pad2)") (class "Default")
      (node (ref "C225") (pin "2") (pinfunction "2_2") (pintype "passive"))
      (node (ref "C226") (pin "1") (pinfunction "1_1") (pintype "passive"))
      (node (ref "R152") (pin "2") (pinfunction "2_2") (pintype "passive"))
      (node (ref "R153") (pin "2") (pinfunction "2_2") (pintype "passive"))
    )
    (net (code "69") (name "Net-(C227-Pad2)") (class "Default")
      (node (ref "C227") (pin "2") (pinfunction "2_2") (pintype "passive"))
      (node (ref "C228") (pin "2") (pinfunction "2_2") (pintype "passive"))
      (node (ref "R155") (pin "1") (pinfunction "1_1") (pintype "passive"))
      (node (ref "R157") (pin "2") (pinfunction "2_2") (pintype "passive"))
    )
    (net (code "70") (name "Net-(IC28-SEL)") (class "Default")
      (node (ref "IC28") (pin "10") (pinfunction "SEL_10") (pintype "input"))
      (node (ref "R138") (pin "2") (pinfunction "2_2") (pintype "passive"))
      (node (ref "VT5") (pin "D") (pinfunction "D_D") (pintype "passive"))
    )
    (net (code "71") (name "Net-(IC30-BT)") (class "Default")
      (node (ref "IC30") (pin "9") (pinfunction "BT_9") (pintype "input"))
      (node (ref "R144") (pin "2") (pinfunction "2_2") (pintype "passive"))
    )
    (net (code "72") (name "Net-(IC30-REGEN)") (class "Default")
      (node (ref "IC30") (pin "23") (pinfunction "REGEN_23") (pintype "input"))
      (node (ref "R147") (pin "2") (pinfunction "2_2") (pintype "passive"))
      (node (ref "R148") (pin "2") (pinfunction "2_2") (pintype "passive"))
    )
    (net (code "73") (name "Net-(IC30-RST)") (class "Default")
      (node (ref "IC30") (pin "25") (pinfunction "RST_25") (pintype "input"))
      (node (ref "R146") (pin "2") (pinfunction "2_2") (pintype "passive"))
      (node (ref "R148") (pin "1") (pinfunction "1_1") (pintype "passive"))
      (node (ref "R149") (pin "2") (pinfunction "2_2") (pintype "passive"))
    )
    (net (code "74") (name "Net-(IC32-VCC)") (class "Default")
      (node (ref "C229") (pin "2") (pinfunction "2_2") (pintype "passive"))
      (node (ref "C230") (pin "1") (pinfunction "1_1") (pintype "passive"))
      (node (ref "FR41") (pin "1") (pinfunction "1_1") (pintype "passive"))
      (node (ref "IC32") (pin "5") (pinfunction "VCC_5") (pintype "power_in"))
    )
    (net (code "75") (name "Net-(IC32-Y1)") (class "Default")
      (node (ref "IC32") (pin "6") (pinfunction "Y1_6") (pintype "output"))
      (node (ref "R152") (pin "1") (pinfunction "1_1") (pintype "passive"))
    )
    (net (code "76") (name "Net-(IC32-Y2)") (class "Default")
      (node (ref "IC32") (pin "4") (pinfunction "Y2_4") (pintype "output"))
      (node (ref "R157") (pin "1") (pinfunction "1_1") (pintype "passive"))
    )
    (net (code "77") (name "Net-(IC33-FAULT)") (class "Default")
      (node (ref "IC33") (pin "4") (pinfunction "FAULT_4") (pintype "output"))
      (node (ref "R159") (pin "2") (pinfunction "2_2") (pintype "passive"))
    )
    (net (code "78") (name "Net-(IC33-ILIM)") (class "Default")
      (node (ref "IC33") (pin "5") (pinfunction "ILIM_5") (pintype "input"))
      (node (ref "R160") (pin "1") (pinfunction "1_1") (pintype "passive"))
    )
    (net (code "79") (name "Net-(J15-Shell)") (class "Default")
      (node (ref "C216") (pin "1") (pinfunction "1_1") (pintype "passive"))
      (node (ref "J15") (pin "6") (pinfunction "Shell_6") (pintype "passive"))
      (node (ref "R141") (pin "1") (pinfunction "1_1") (pintype "passive"))
    )
    (net (code "80") (name "Net-(J16-Card_Detect{slash}_Data_Line_[Bit_3])") (class "Default")
      (node (ref "J16") (pin "2") (pinfunction "Card_Detect/_Data_Line_[Bit_3]_2") (pintype "passive"))
      (node (ref "R136") (pin "2") (pinfunction "2_2") (pintype "passive"))
    )
    (net (code "81") (name "Net-(J16-Clock)") (class "Default")
      (node (ref "J16") (pin "5") (pinfunction "Clock_5") (pintype "passive"))
      (node (ref "R139") (pin "2") (pinfunction "2_2") (pintype "passive"))
    )
    (net (code "82") (name "Net-(J16-Command{slash}Response)") (class "Default")
      (node (ref "J16") (pin "3") (pinfunction "Command/Response_3") (pintype "passive"))
      (node (ref "R137") (pin "2") (pinfunction "2_2") (pintype "passive"))
    )
    (net (code "83") (name "Net-(J16-Data_Line_[Bit_0])") (class "Default")
      (node (ref "J16") (pin "7") (pinfunction "Data_Line_[Bit_0]_7") (pintype "passive"))
      (node (ref "R140") (pin "2") (pinfunction "2_2") (pintype "passive"))
    )
    (net (code "84") (name "Net-(J16-Data_Line_[Bit_1])") (class "Default")
      (node (ref "J16") (pin "8") (pinfunction "Data_Line_[Bit_1]_8") (pintype "passive"))
      (node (ref "R142") (pin "2") (pinfunction "2_2") (pintype "passive"))
    )
    (net (code "85") (name "Net-(J16-Date_Line_[Bit_2])") (class "Default")
      (node (ref "J16") (pin "1") (pinfunction "Date_Line_[Bit_2]_1") (pintype "passive"))
      (node (ref "R135") (pin "2") (pinfunction "2_2") (pintype "passive"))
    )
    (net (code "86") (name "Net-(J16-Supply_Voltage)") (class "Default")
      (node (ref "C213") (pin "2") (pinfunction "2_2") (pintype "passive"))
      (node (ref "C214") (pin "1") (pinfunction "1_1") (pintype "passive"))
      (node (ref "FR40") (pin "1") (pinfunction "1_1") (pintype "passive"))
      (node (ref "J16") (pin "4") (pinfunction "Supply_Voltage_4") (pintype "passive"))
    )
    (net (code "87") (name "RAPI_VDAC") (class "Default")
      (node (ref "VD2") (pin "2") (pinfunction "2_2") (pintype "passive"))
    )
    (net (code "88") (name "VCC1P8") (class "Default")
      (node (ref "C218") (pin "2") (pinfunction "2_2") (pintype "passive"))
      (node (ref "IC30") (pin "17") (pinfunction "VDD_REGIN_17") (pintype "passive"))
      (node (ref "R146") (pin "1") (pinfunction "1_1") (pintype "passive"))
      (node (ref "R147") (pin "1") (pinfunction "1_1") (pintype "passive"))
      (node (ref "R151") (pin "1") (pinfunction "1_1") (pintype "passive"))
    )
    (net (code "89") (name "VCC3P3") (class "Default")
      (node (ref "C212") (pin "1") (pinfunction "1_1") (pintype "passive"))
      (node (ref "FR41") (pin "2") (pinfunction "2_2") (pintype "passive"))
      (node (ref "J17") (pin "4") (pinfunction "4_4") (pintype "passive"))
      (node (ref "J22") (pin "14") (pinfunction "14_14") (pintype "passive"))
      (node (ref "J22") (pin "15") (pinfunction "15_15") (pintype "passive"))
      (node (ref "J23") (pin "15") (pinfunction "15_15") (pintype "passive"))
      (node (ref "R150") (pin "1") (pinfunction "1_1") (pintype "passive"))
    )
    (net (code "90") (name "VCC3P3_2") (class "Default")
      (node (ref "C215") (pin "1") (pinfunction "1_1") (pintype "passive"))
      (node (ref "C217") (pin "1") (pinfunction "1_1") (pintype "passive"))
      (node (ref "C219") (pin "1") (pinfunction "1_1") (pintype "passive"))
      (node (ref "C220") (pin "2") (pinfunction "2_2") (pintype "passive"))
      (node (ref "C221") (pin "2") (pinfunction "2_2") (pintype "passive"))
      (node (ref "C222") (pin "2") (pinfunction "2_2") (pintype "passive"))
      (node (ref "C223") (pin "2") (pinfunction "2_2") (pintype "passive"))
      (node (ref "C224") (pin "2") (pinfunction "2_2") (pintype "passive"))
      (node (ref "FR40") (pin "2") (pinfunction "2_2") (pintype "passive"))
      (node (ref "IC28") (pin "9") (pinfunction "VCC_9") (pintype "power_in"))
      (node (ref "IC29") (pin "9") (pinfunction "VCC_9") (pintype "power_in"))
      (node (ref "IC30") (pin "10") (pinfunction "VDD_ANA_10") (pintype "power_in"))
      (node (ref "IC30") (pin "15") (pinfunction "VDD_SDIO_15") (pintype "power_in"))
      (node (ref "IC30") (pin "19") (pinfunction "VDD_PADS_19") (pintype "power_in"))
      (node (ref "IC30") (pin "28") (pinfunction "VDD_PA_28") (pintype "power_in"))
      (node (ref "IC31") (pin "9") (pinfunction "VCC_9") (pintype "power_in"))
      (node (ref "J18") (pin "2") (pinfunction "2_2") (pintype "passive"))
      (node (ref "R138") (pin "1") (pinfunction "1_1") (pintype "passive"))
      (node (ref "R143") (pin "2") (pinfunction "2_2") (pintype "passive"))
    )
    (net (code "91") (name "VCC5P0") (class "Default")
      (node (ref "C231") (pin "2") (pinfunction "2_2") (pintype "passive"))
      (node (ref "C233") (pin "1") (pinfunction "1_1") (pintype "passive"))
      (node (ref "IC33") (pin "1") (pinfunction "IN_1") (pintype "input"))
      (node (ref "IC33") (pin "3") (pinfunction "EN_3") (pintype "input"))
      (node (ref "R158") (pin "2") (pinfunction "2_2") (pintype "passive"))
      (node (ref "R159") (pin "1") (pinfunction "1_1") (pintype "passive"))
    )
    (net (code "92") (name "VCC5P0_HDMI") (class "Default")
      (node (ref "C232") (pin "2") (pinfunction "2_2") (pintype "passive"))
      (node (ref "C234") (pin "1") (pinfunction "1_1") (pintype "passive"))
      (node (ref "IC33") (pin "6") (pinfunction "OUT_6") (pintype "output"))
      (node (ref "J19") (pin "18") (pinfunction "+5V_Power_18") (pintype "passive"))
      (node (ref "R158") (pin "1") (pinfunction "1_1") (pintype "passive"))
      (node (ref "VD1") (pin "A1") (pinfunction "5V_A1") (pintype "passive"))
      (node (ref "VD1") (pin "C1") (pinfunction "RPU_C1") (pintype "passive"))
      (node (ref "VT7") (pin "G") (pinfunction "G_G") (pintype "passive"))
    )
    (net (code "93") (name "VCC5P0_USB_EXT") (class "Default")
      (node (ref "J15") (pin "1") (pinfunction "VBUS_1") (pintype "passive"))
    )
    (net (code "94") (name "unconnected-(IC30-PIO[0]-Pad22)") (class "Default")
      (node (ref "IC30") (pin "22") (pinfunction "PIO[0]_22") (pintype "bidirectional+no_connect"))
    )
    (net (code "95") (name "unconnected-(IC30-PIO[1]-Pad24)") (class "Default")
      (node (ref "IC30") (pin "24") (pinfunction "PIO[1]_24") (pintype "bidirectional+no_connect"))
    )
    (net (code "96") (name "unconnected-(IC30-PIO[2]-Pad16)") (class "Default")
      (node (ref "IC30") (pin "16") (pinfunction "PIO[2]_16") (pintype "bidirectional+no_connect"))
    )
    (net (code "97") (name "unconnected-(IC30-PIO[3]-Pad20)") (class "Default")
      (node (ref "IC30") (pin "20") (pinfunction "PIO[3]_20") (pintype "bidirectional+no_connect"))
    )
    (net (code "98") (name "unconnected-(IC30-PIO[4]-Pad18)") (class "Default")
      (node (ref "IC30") (pin "18") (pinfunction "PIO[4]_18") (pintype "bidirectional+no_connect"))
    )
    (net (code "99") (name "unconnected-(IC30-SPI_CLK-Pad12)") (class "Default")
      (node (ref "IC30") (pin "12") (pinfunction "SPI_CLK_12") (pintype "input+no_connect"))
    )
    (net (code "100") (name "unconnected-(IC30-SPI_CS-Pad26)") (class "Default")
      (node (ref "IC30") (pin "26") (pinfunction "SPI_CS_26") (pintype "input+no_connect"))
    )
    (net (code "101") (name "unconnected-(IC30-SPI_MISO-Pad11)") (class "Default")
      (node (ref "IC30") (pin "11") (pinfunction "SPI_MISO_11") (pintype "output+no_connect"))
    )
    (net (code "102") (name "unconnected-(IC30-SPI_MOSI-Pad13)") (class "Default")
      (node (ref "IC30") (pin "13") (pinfunction "SPI_MOSI_13") (pintype "input+no_connect"))
    )
    (net (code "103") (name "unconnected-(J15-ID-Pad4)") (class "Default")
      (node (ref "J15") (pin "4") (pinfunction "ID_4") (pintype "passive+no_connect"))
    )
    (net (code "104") (name "unconnected-(J19-Reserved{slash}HEC_Data--Pad14)") (class "Default")
      (node (ref "J19") (pin "14") (pinfunction "Reserved/HEC_Data-_14") (pintype "passive+no_connect"))
    )
    (net (code "105") (name "unconnected-(JMP2-Pad1)") (class "Default")
      (node (ref "JMP2") (pin "1") (pinfunction "1_1") (pintype "passive"))
    )
    (net (code "106") (name "unconnected-(JMP2-Pad2)") (class "Default")
      (node (ref "JMP2") (pin "2") (pinfunction "2_2") (pintype "passive"))
    )
    (net (code "107") (name "unconnected-(VD1-RPU2-PadB1)") (class "Default")
      (node (ref "VD1") (pin "B1") (pinfunction "RPU2_B1") (pintype "passive+no_connect"))
    )
  )
)
